# blink.net
KiCad netlist of a schematic drawn in EAGLE
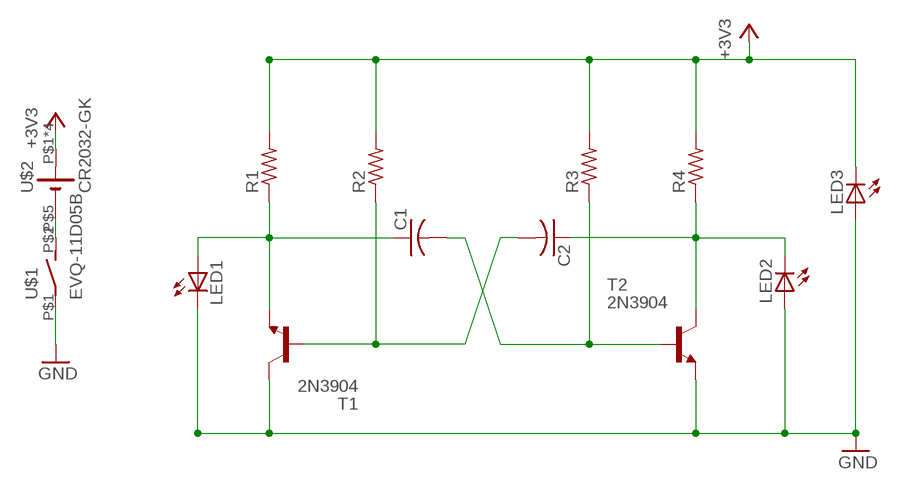
[diagram p0: schematic, sheet 1]

(export (version "E")
  (design (tool "Eeschema 10.0.6"))
  (components
    (comp (ref "C1")
      (value "C-US025-030X050")
      (footprint "eagle-import:C025-030X050")
      (libsource (lib "eagle-import") (part "C-US025-030X050"))
    )
    (comp (ref "C2")
      (value "C-US025-030X050")
      (footprint "eagle-import:C025-030X050")
      (libsource (lib "eagle-import") (part "C-US025-030X050"))
    )
    (comp (ref "LED1")
      (value "LED3MM")
      (footprint "eagle-import:LED3MM")
      (libsource (lib "eagle-import") (part "LED3MM"))
    )
    (comp (ref "LED2")
      (value "LED3MM")
      (footprint "eagle-import:LED3MM")
      (libsource (lib "eagle-import") (part "LED3MM"))
    )
    (comp (ref "LED3")
      (value "LED5MM")
      (footprint "eagle-import:LED5MM")
      (libsource (lib "eagle-import") (part "LED5MM"))
    )
    (comp (ref "R1")
      (value "R-US_0207/7")
      (footprint "eagle-import:0207_7")
      (libsource (lib "eagle-import") (part "R-US_0207/7"))
    )
    (comp (ref "R2")
      (value "R-US_0207/7")
      (footprint "eagle-import:0207_7")
      (libsource (lib "eagle-import") (part "R-US_0207/7"))
    )
    (comp (ref "R3")
      (value "R-US_0207/7")
      (footprint "eagle-import:0207_7")
      (libsource (lib "eagle-import") (part "R-US_0207/7"))
    )
    (comp (ref "R4")
      (value "R-US_0207/7")
      (footprint "eagle-import:0207_7")
      (libsource (lib "eagle-import") (part "R-US_0207/7"))
    )
    (comp (ref "T1")
      (value "2N3904")
      (footprint "eagle-import:TO92")
      (libsource (lib "eagle-import") (part "2N3904"))
    )
    (comp (ref "T2")
      (value "2N3904")
      (footprint "eagle-import:TO92")
      (libsource (lib "eagle-import") (part "2N3904"))
    )
    (comp (ref "U$1")
      (value "EVQ-11D05B")
      (footprint "eagle-import:SPST-5MM")
      (libsource (lib "eagle-import") (part "EVQ-11D05B"))
    )
    (comp (ref "U$2")
      (value "CR2032-GK")
      (footprint "eagle-import:BAT-HLD-001-THM")
      (libsource (lib "eagle-import") (part "CR2032-GK"))
    )
  )
  (nets
    (net (code "1") (name "+3V3") (class "Default")
      (node (ref "LED3") (pin "K") (pinfunction "C_K") (pintype "passive"))
      (node (ref "R1") (pin "2") (pinfunction "2_2") (pintype "passive"))
      (node (ref "R2") (pin "2") (pinfunction "2_2") (pintype "passive"))
      (node (ref "R3") (pin "2") (pinfunction "2_2") (pintype "passive"))
      (node (ref "R4") (pin "2") (pinfunction "2_2") (pintype "passive"))
      (node (ref "U$2") (pin "P$1") (pinfunction "+_P$1") (pintype "passive"))
      (node (ref "U$2") (pin "P$2") (pinfunction "+_P$2") (pintype "passive"))
      (node (ref "U$2") (pin "P$3") (pinfunction "+_P$3") (pintype "passive"))
      (node (ref "U$2") (pin "P$4") (pinfunction "+_P$4") (pintype "passive"))
    )
    (net (code "2") (name "GND") (class "Default")
      (node (ref "LED1") (pin "K") (pinfunction "C_K") (pintype "passive"))
      (node (ref "LED2") (pin "A") (pinfunction "A_A") (pintype "passive"))
      (node (ref "LED3") (pin "A") (pinfunction "A_A") (pintype "passive"))
      (node (ref "T1") (pin "1") (pinfunction "C_1") (pintype "passive"))
      (node (ref "T2") (pin "3") (pinfunction "E_3") (pintype "passive"))
      (node (ref "U$1") (pin "P$1") (pinfunction "P_P$1") (pintype "passive"))
    )
    (net (code "3") (name "Net-(LED2-C)") (class "Default")
      (node (ref "C2") (pin "1") (pinfunction "1_1") (pintype "passive"))
      (node (ref "LED2") (pin "K") (pinfunction "C_K") (pintype "passive"))
      (node (ref "R4") (pin "1") (pinfunction "1_1") (pintype "passive"))
      (node (ref "T2") (pin "1") (pinfunction "C_1") (pintype "passive"))
    )
    (net (code "4") (name "Net-(T1-B)") (class "Default")
      (node (ref "C2") (pin "2") (pinfunction "2_2") (pintype "passive"))
      (node (ref "R2") (pin "1") (pinfunction "1_1") (pintype "passive"))
      (node (ref "T1") (pin "2") (pinfunction "B_2") (pintype "passive"))
    )
    (net (code "5") (name "Net-(T1-E)") (class "Default")
      (node (ref "C1") (pin "1") (pinfunction "1_1") (pintype "passive"))
      (node (ref "LED1") (pin "A") (pinfunction "A_A") (pintype "passive"))
      (node (ref "R1") (pin "1") (pinfunction "1_1") (pintype "passive"))
      (node (ref "T1") (pin "3") (pinfunction "E_3") (pintype "passive"))
    )
    (net (code "6") (name "Net-(T2-B)") (class "Default")
      (node (ref "C1") (pin "2") (pinfunction "2_2") (pintype "passive"))
      (node (ref "R3") (pin "1") (pinfunction "1_1") (pintype "passive"))
      (node (ref "T2") (pin "2") (pinfunction "B_2") (pintype "passive"))
    )
    (net (code "7") (name "Net-(U$1-S)") (class "Default")
      (node (ref "U$1") (pin "P$2") (pinfunction "S_P$2") (pintype "passive"))
      (node (ref "U$2") (pin "P$5") (pinfunction "-_P$5") (pintype "passive"))
    )
  )
)
